# Cansat2019_1516_Payload_SectionA_v04.net
KiCad netlist of a schematic drawn in EAGLE
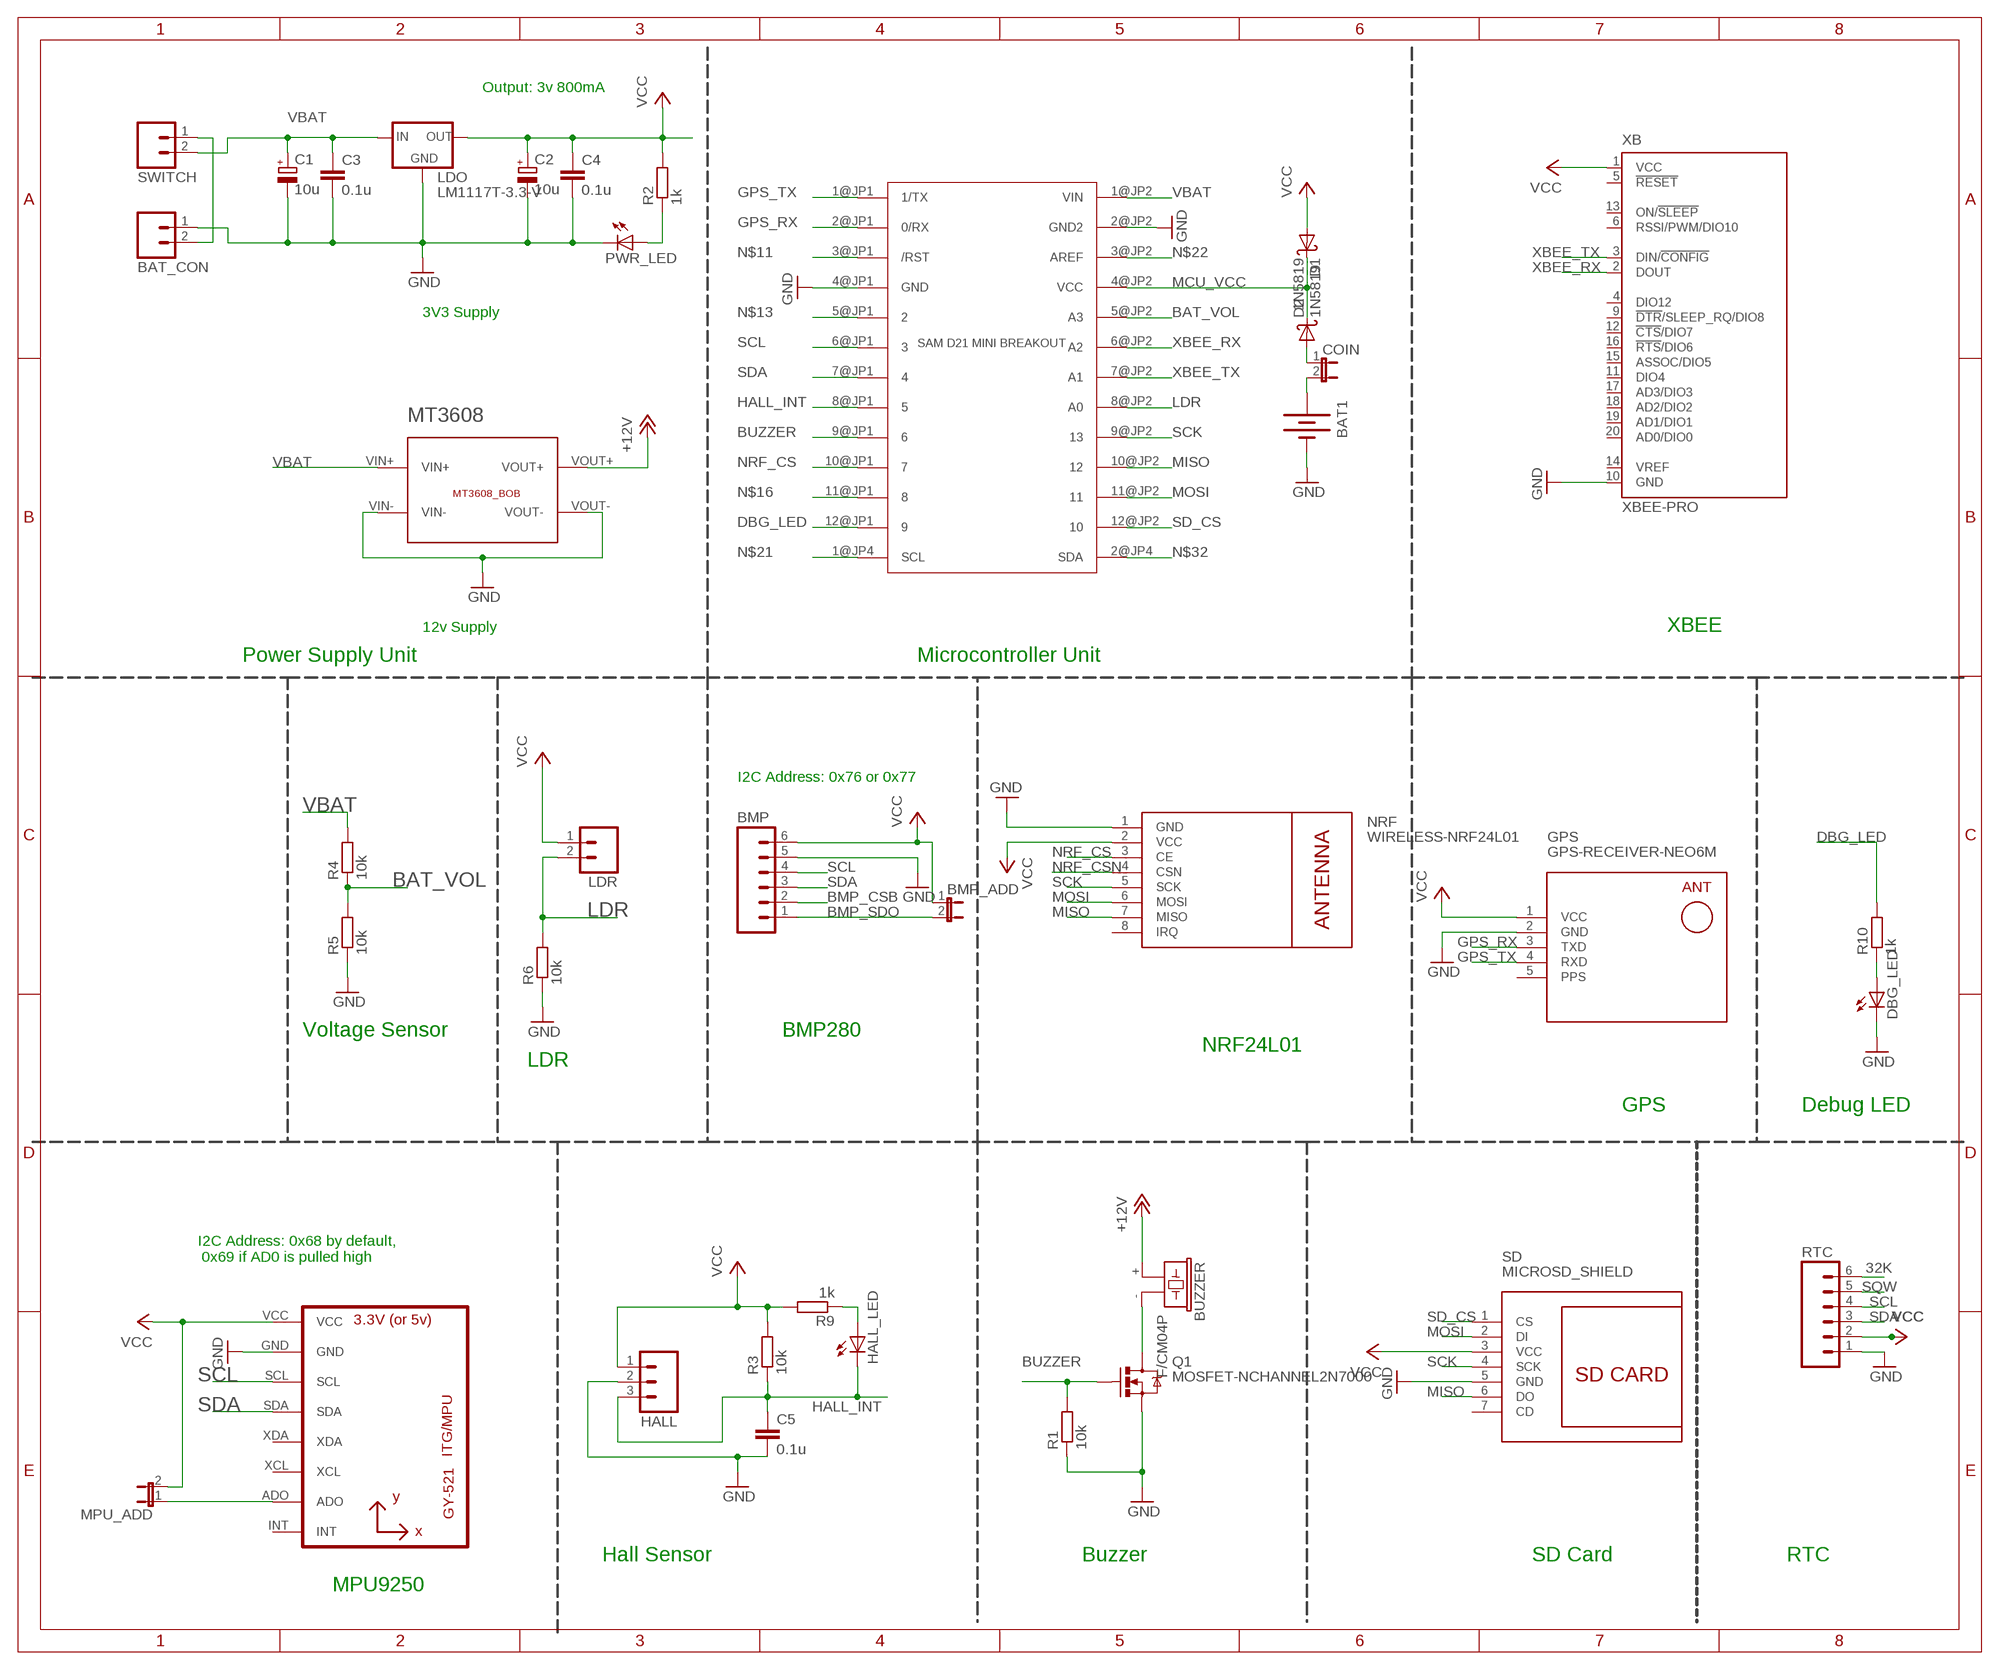
[diagram p0: schematic, sheet 1]

(export (version "E")
  (design (tool "Eeschema 10.0.6"))
  (components
    (comp (ref "BAT1")
      (value "BATTERY20PTH")
      (footprint "eagle-import:BATTCOM_20MM_PTH")
      (libsource (lib "eagle-import") (part "BATTERY20PTH"))
    )
    (comp (ref "BAT_CON")
      (value "M02")
      (footprint "eagle-import:02P")
      (libsource (lib "eagle-import") (part "M02"))
    )
    (comp (ref "BMP")
      (value "M06")
      (footprint "eagle-import:06P")
      (libsource (lib "eagle-import") (part "M06"))
    )
    (comp (ref "BMP_ADD")
      (value "JUMPER-2PTH")
      (footprint "eagle-import:1X02")
      (libsource (lib "eagle-import") (part "JUMPER-2PTH"))
    )
    (comp (ref "BUZZER")
      (value "F/CM04P")
      (footprint "eagle-import:F_CM04P")
      (libsource (lib "eagle-import") (part "F/CM04P"))
    )
    (comp (ref "C1")
      (value "10u")
      (footprint "eagle-import:E2,5-6")
      (libsource (lib "eagle-import") (part "CPOL-EUE2.5-6"))
    )
    (comp (ref "C2")
      (value "10u")
      (footprint "eagle-import:E2,5-6")
      (libsource (lib "eagle-import") (part "CPOL-EUE2.5-6"))
    )
    (comp (ref "C3")
      (value "0.1u")
      (footprint "eagle-import:C025-025X050")
      (libsource (lib "eagle-import") (part "C-EU025-025X050"))
    )
    (comp (ref "C4")
      (value "0.1u")
      (footprint "eagle-import:C025-025X050")
      (libsource (lib "eagle-import") (part "C-EU025-025X050"))
    )
    (comp (ref "C5")
      (value "0.1u")
      (footprint "eagle-import:C025-025X050")
      (libsource (lib "eagle-import") (part "C-EU025-025X050"))
    )
    (comp (ref "COIN")
      (value "JUMPER-2PTH")
      (footprint "eagle-import:1X02")
      (libsource (lib "eagle-import") (part "JUMPER-2PTH"))
    )
    (comp (ref "D1")
      (value "1N5819")
      (footprint "eagle-import:DO41-10")
      (libsource (lib "eagle-import") (part "1N5819"))
    )
    (comp (ref "D2")
      (value "1N5819")
      (footprint "eagle-import:DO41-10")
      (libsource (lib "eagle-import") (part "1N5819"))
    )
    (comp (ref "DBG_LED")
      (value "LED3MM")
      (footprint "eagle-import:LED3MM")
      (libsource (lib "eagle-import") (part "LED3MM"))
    )
    (comp (ref "GPS")
      (value "GPS-RECEIVER-NEO6M")
      (footprint "eagle-import:GPS-RECEIVER-NEO6M")
      (libsource (lib "eagle-import") (part "GPS-RECEIVER-NEO6M"))
    )
    (comp (ref "HALL")
      (value "M03")
      (footprint "eagle-import:03P")
      (libsource (lib "eagle-import") (part "M03"))
    )
    (comp (ref "HALL_LED")
      (value "LED3MM")
      (footprint "eagle-import:LED3MM")
      (libsource (lib "eagle-import") (part "LED3MM"))
    )
    (comp (ref "LDO")
      (value "LM1117T-3.3-V")
      (footprint "eagle-import:TO220V")
      (libsource (lib "eagle-import") (part "LM1117T--V3.3"))
    )
    (comp (ref "LDR")
      (value "M02")
      (footprint "eagle-import:02P")
      (libsource (lib "eagle-import") (part "M02"))
    )
    (comp (ref "MPU")
      (value "GY-521MPU6050")
      (footprint "eagle-import:GY-521")
      (libsource (lib "eagle-import") (part "GY-521MPU6050"))
    )
    (comp (ref "MPU_ADD")
      (value "JUMPER-2PTH")
      (footprint "eagle-import:1X02")
      (libsource (lib "eagle-import") (part "JUMPER-2PTH"))
    )
    (comp (ref "MT3608")
      (value "MT3608_BOB")
      (footprint "eagle-import:MT3608_BOB")
      (libsource (lib "eagle-import") (part "MT3608_BOB"))
    )
    (comp (ref "NRF")
      (value "WIRELESS-NRF24L01")
      (footprint "eagle-import:WIRELESS-NRF24L01")
      (libsource (lib "eagle-import") (part "WIRELESS-NRF24L01"))
    )
    (comp (ref "PWR_LED")
      (value "LED3MM")
      (footprint "eagle-import:LED3MM")
      (libsource (lib "eagle-import") (part "LED3MM"))
    )
    (comp (ref "Q1")
      (value "MOSFET-NCHANNEL2N7000")
      (footprint "eagle-import:TO-92")
      (libsource (lib "eagle-import") (part "MOSFET-NCHANNEL2N7000"))
    )
    (comp (ref "R1")
      (value "10k")
      (footprint "eagle-import:0204_7")
      (libsource (lib "eagle-import") (part "R-EU_0204/7"))
    )
    (comp (ref "R2")
      (value "1k")
      (footprint "eagle-import:0204_7")
      (libsource (lib "eagle-import") (part "R-EU_0204/7"))
    )
    (comp (ref "R3")
      (value "10k")
      (footprint "eagle-import:0204_7")
      (libsource (lib "eagle-import") (part "R-EU_0204/7"))
    )
    (comp (ref "R4")
      (value "10k")
      (footprint "eagle-import:0204_7")
      (libsource (lib "eagle-import") (part "R-EU_0204/7"))
    )
    (comp (ref "R5")
      (value "10k")
      (footprint "eagle-import:0204_7")
      (libsource (lib "eagle-import") (part "R-EU_0204/7"))
    )
    (comp (ref "R6")
      (value "10k")
      (footprint "eagle-import:0204_7")
      (libsource (lib "eagle-import") (part "R-EU_0204/7"))
    )
    (comp (ref "R9")
      (value "1k")
      (footprint "eagle-import:0204_7")
      (libsource (lib "eagle-import") (part "R-EU_0204/7"))
    )
    (comp (ref "R10")
      (value "1k")
      (footprint "eagle-import:0204_7")
      (libsource (lib "eagle-import") (part "R-EU_0204/7"))
    )
    (comp (ref "RTC")
      (value "M06")
      (footprint "eagle-import:06P")
      (libsource (lib "eagle-import") (part "M06"))
    )
    (comp (ref "SAMD")
      (value "SAM_D21_MINI_BREAKOUT")
      (footprint "eagle-import:JP1_SPARKFUN-SAMD21-MINI-BREAKOUT-V10")
      (libsource (lib "eagle-import") (part "SAM_D21_MINI_BREAKOUT"))
    )
    (comp (ref "SD")
      (value "MICROSD_SHIELD")
      (footprint "eagle-import:MICROSD_SHIELD")
      (libsource (lib "eagle-import") (part "MICROSD_SHIELD"))
    )
    (comp (ref "SWITCH")
      (value "M02")
      (footprint "eagle-import:02P")
      (libsource (lib "eagle-import") (part "M02"))
    )
    (comp (ref "XB")
      (value "XBEE-PRO")
      (footprint "eagle-import:XBEE-PRO")
      (fields (field (name "MPN") "XBP24-AWI-001"))
      (libsource (lib "eagle-import") (part "XBEE-PRO"))
    )
  )
  (nets
    (net (code "1") (name "+12V") (class "Default")
      (node (ref "BUZZER") (pin "+") (pinfunction "1_+") (pintype "passive"))
      (node (ref "MT3608") (pin "VOUT+") (pinfunction "VOUT+_VOUT+") (pintype "bidirectional"))
    )
    (net (code "2") (name "/32K") (class "Default")
      (node (ref "RTC") (pin "6") (pinfunction "6_6") (pintype "passive"))
    )
    (net (code "3") (name "/BAT_VOL") (class "Default")
      (node (ref "R4") (pin "1") (pinfunction "1_1") (pintype "passive"))
      (node (ref "R5") (pin "2") (pinfunction "2_2") (pintype "passive"))
      (node (ref "SAMD") (pin "5@JP2") (pinfunction "A3_5@JP2") (pintype "bidirectional"))
    )
    (net (code "4") (name "/BMP_CSB") (class "Default")
      (node (ref "BMP") (pin "2") (pinfunction "2_2") (pintype "passive"))
    )
    (net (code "5") (name "/BMP_SDO") (class "Default")
      (node (ref "BMP") (pin "1") (pinfunction "1_1") (pintype "passive"))
      (node (ref "BMP_ADD") (pin "2") (pinfunction "2_2") (pintype "passive"))
    )
    (net (code "6") (name "/BUZZER") (class "Default")
      (node (ref "Q1") (pin "2") (pinfunction "G_2") (pintype "passive"))
      (node (ref "R1") (pin "2") (pinfunction "2_2") (pintype "passive"))
      (node (ref "SAMD") (pin "9@JP1") (pinfunction "6_9@JP1") (pintype "bidirectional"))
    )
    (net (code "7") (name "/DBG_LED") (class "Default")
      (node (ref "R10") (pin "2") (pinfunction "2_2") (pintype "passive"))
      (node (ref "SAMD") (pin "12@JP1") (pinfunction "9_12@JP1") (pintype "bidirectional"))
    )
    (net (code "8") (name "/GPS_RX") (class "Default")
      (node (ref "GPS") (pin "3") (pinfunction "TXD_3") (pintype "bidirectional"))
      (node (ref "SAMD") (pin "2@JP1") (pinfunction "0/RX_2@JP1") (pintype "bidirectional"))
    )
    (net (code "9") (name "/GPS_TX") (class "Default")
      (node (ref "GPS") (pin "4") (pinfunction "RXD_4") (pintype "power_in"))
      (node (ref "SAMD") (pin "1@JP1") (pinfunction "1/TX_1@JP1") (pintype "bidirectional"))
    )
    (net (code "10") (name "/HALL_INT") (class "Default")
      (node (ref "C5") (pin "1") (pinfunction "1_1") (pintype "passive"))
      (node (ref "HALL") (pin "3") (pinfunction "3_3") (pintype "passive"))
      (node (ref "HALL_LED") (pin "K") (pinfunction "C_K") (pintype "passive"))
      (node (ref "R3") (pin "1") (pinfunction "1_1") (pintype "passive"))
      (node (ref "SAMD") (pin "8@JP1") (pinfunction "5_8@JP1") (pintype "bidirectional"))
    )
    (net (code "11") (name "/LDR") (class "Default")
      (node (ref "LDR") (pin "2") (pinfunction "2_2") (pintype "passive"))
      (node (ref "R6") (pin "2") (pinfunction "2_2") (pintype "passive"))
      (node (ref "SAMD") (pin "8@JP2") (pinfunction "A0_8@JP2") (pintype "bidirectional"))
    )
    (net (code "12") (name "/MCU_VCC") (class "Default")
      (node (ref "D1") (pin "C") (pinfunction "C_C") (pintype "passive"))
      (node (ref "D2") (pin "C") (pinfunction "C_C") (pintype "passive"))
      (node (ref "SAMD") (pin "4@JP2") (pinfunction "VCC_4@JP2") (pintype "power_in"))
    )
    (net (code "13") (name "/MISO") (class "Default")
      (node (ref "NRF") (pin "7") (pinfunction "MISO_7") (pintype "bidirectional"))
      (node (ref "SAMD") (pin "10@JP2") (pinfunction "12_10@JP2") (pintype "bidirectional"))
      (node (ref "SD") (pin "6") (pinfunction "DO_6") (pintype "bidirectional"))
    )
    (net (code "14") (name "/MOSI") (class "Default")
      (node (ref "NRF") (pin "6") (pinfunction "MOSI_6") (pintype "bidirectional"))
      (node (ref "SAMD") (pin "11@JP2") (pinfunction "11_11@JP2") (pintype "bidirectional"))
      (node (ref "SD") (pin "2") (pinfunction "DI_2") (pintype "bidirectional"))
    )
    (net (code "15") (name "/N$11") (class "Default")
      (node (ref "SAMD") (pin "3@JP1") (pinfunction "/RST_3@JP1") (pintype "input"))
    )
    (net (code "16") (name "/N$13") (class "Default")
      (node (ref "SAMD") (pin "5@JP1") (pinfunction "2_5@JP1") (pintype "bidirectional"))
    )
    (net (code "17") (name "/N$16") (class "Default")
      (node (ref "SAMD") (pin "11@JP1") (pinfunction "8_11@JP1") (pintype "bidirectional"))
    )
    (net (code "18") (name "/N$21") (class "Default")
      (node (ref "SAMD") (pin "1@JP4") (pinfunction "SCL_1@JP4") (pintype "bidirectional"))
    )
    (net (code "19") (name "/N$22") (class "Default")
      (node (ref "SAMD") (pin "3@JP2") (pinfunction "AREF_3@JP2") (pintype "power_in"))
    )
    (net (code "20") (name "/N$32") (class "Default")
      (node (ref "SAMD") (pin "2@JP4") (pinfunction "SDA_2@JP4") (pintype "bidirectional"))
    )
    (net (code "21") (name "/NRF_CS") (class "Default")
      (node (ref "NRF") (pin "3") (pinfunction "CE_3") (pintype "bidirectional"))
      (node (ref "SAMD") (pin "10@JP1") (pinfunction "7_10@JP1") (pintype "bidirectional"))
    )
    (net (code "22") (name "/NRF_CSN") (class "Default")
      (node (ref "NRF") (pin "4") (pinfunction "CSN_4") (pintype "bidirectional"))
    )
    (net (code "23") (name "/PPS") (class "Default")
      (node (ref "GPS") (pin "5") (pinfunction "PPS_5") (pintype "power_in"))
    )
    (net (code "24") (name "/SCK") (class "Default")
      (node (ref "NRF") (pin "5") (pinfunction "SCK_5") (pintype "bidirectional"))
      (node (ref "SAMD") (pin "9@JP2") (pinfunction "13_9@JP2") (pintype "bidirectional"))
      (node (ref "SD") (pin "4") (pinfunction "SCK_4") (pintype "bidirectional"))
    )
    (net (code "25") (name "/SCL") (class "Default")
      (node (ref "BMP") (pin "4") (pinfunction "4_4") (pintype "passive"))
      (node (ref "MPU") (pin "SCL") (pinfunction "SCL_SCL") (pintype "bidirectional"))
      (node (ref "RTC") (pin "4") (pinfunction "4_4") (pintype "passive"))
      (node (ref "SAMD") (pin "6@JP1") (pinfunction "3_6@JP1") (pintype "bidirectional"))
    )
    (net (code "26") (name "/SDA") (class "Default")
      (node (ref "BMP") (pin "3") (pinfunction "3_3") (pintype "passive"))
      (node (ref "MPU") (pin "SDA") (pinfunction "SDA_SDA") (pintype "bidirectional"))
      (node (ref "RTC") (pin "3") (pinfunction "3_3") (pintype "passive"))
      (node (ref "SAMD") (pin "7@JP1") (pinfunction "4_7@JP1") (pintype "bidirectional"))
    )
    (net (code "27") (name "/SD_CS") (class "Default")
      (node (ref "SAMD") (pin "12@JP2") (pinfunction "10_12@JP2") (pintype "bidirectional"))
      (node (ref "SD") (pin "1") (pinfunction "CS_1") (pintype "bidirectional"))
    )
    (net (code "28") (name "/SQW") (class "Default")
      (node (ref "RTC") (pin "5") (pinfunction "5_5") (pintype "passive"))
    )
    (net (code "29") (name "/VBAT") (class "Default")
      (node (ref "C1") (pin "+") (pinfunction "+_+") (pintype "passive"))
      (node (ref "C3") (pin "1") (pinfunction "1_1") (pintype "passive"))
      (node (ref "LDO") (pin "3") (pinfunction "IN_3") (pintype "input"))
      (node (ref "MT3608") (pin "VIN+") (pinfunction "VIN+_VIN+") (pintype "bidirectional"))
      (node (ref "R4") (pin "2") (pinfunction "2_2") (pintype "passive"))
      (node (ref "SAMD") (pin "1@JP2") (pinfunction "VIN_1@JP2") (pintype "power_in"))
      (node (ref "SWITCH") (pin "2") (pinfunction "2_2") (pintype "passive"))
    )
    (net (code "30") (name "/XBEE_RX") (class "Default")
      (node (ref "SAMD") (pin "6@JP2") (pinfunction "A2_6@JP2") (pintype "bidirectional"))
      (node (ref "XB") (pin "2") (pinfunction "DOUT_2") (pintype "output"))
    )
    (net (code "31") (name "/XBEE_TX") (class "Default")
      (node (ref "SAMD") (pin "7@JP2") (pinfunction "A1_7@JP2") (pintype "bidirectional"))
      (node (ref "XB") (pin "3") (pinfunction "DIN/~{CONFIG}_3") (pintype "input"))
    )
    (net (code "32") (name "GND") (class "Default")
      (node (ref "BAT1") (pin "2") (pinfunction "-_2") (pintype "power_in"))
      (node (ref "BAT_CON") (pin "1") (pinfunction "1_1") (pintype "passive"))
      (node (ref "BMP") (pin "5") (pinfunction "5_5") (pintype "passive"))
      (node (ref "C1") (pin "-") (pinfunction "-_-") (pintype "passive"))
      (node (ref "C2") (pin "-") (pinfunction "-_-") (pintype "passive"))
      (node (ref "C3") (pin "2") (pinfunction "2_2") (pintype "passive"))
      (node (ref "C4") (pin "2") (pinfunction "2_2") (pintype "passive"))
      (node (ref "C5") (pin "2") (pinfunction "2_2") (pintype "passive"))
      (node (ref "DBG_LED") (pin "K") (pinfunction "C_K") (pintype "passive"))
      (node (ref "GPS") (pin "2") (pinfunction "GND_2") (pintype "bidirectional"))
      (node (ref "HALL") (pin "2") (pinfunction "2_2") (pintype "passive"))
      (node (ref "LDO") (pin "1") (pinfunction "GND_1") (pintype "input"))
      (node (ref "MPU") (pin "GND") (pinfunction "GND_GND") (pintype "bidirectional"))
      (node (ref "MT3608") (pin "VIN-") (pinfunction "VIN-_VIN-") (pintype "bidirectional"))
      (node (ref "MT3608") (pin "VOUT-") (pinfunction "VOUT-_VOUT-") (pintype "bidirectional"))
      (node (ref "NRF") (pin "1") (pinfunction "GND_1") (pintype "power_in"))
      (node (ref "PWR_LED") (pin "K") (pinfunction "C_K") (pintype "passive"))
      (node (ref "Q1") (pin "1") (pinfunction "S_1") (pintype "passive"))
      (node (ref "R1") (pin "1") (pinfunction "1_1") (pintype "passive"))
      (node (ref "R5") (pin "1") (pinfunction "1_1") (pintype "passive"))
      (node (ref "R6") (pin "1") (pinfunction "1_1") (pintype "passive"))
      (node (ref "RTC") (pin "1") (pinfunction "1_1") (pintype "passive"))
      (node (ref "SAMD") (pin "2@JP2") (pinfunction "GND2_2@JP2") (pintype "power_in"))
      (node (ref "SAMD") (pin "4@JP1") (pinfunction "GND_4@JP1") (pintype "power_in"))
      (node (ref "SD") (pin "5") (pinfunction "GND_5") (pintype "power_in"))
      (node (ref "XB") (pin "10") (pinfunction "GND_10") (pintype "power_in"))
    )
    (net (code "33") (name "Net-(BAT1-+)") (class "Default")
      (node (ref "BAT1") (pin "1") (pinfunction "+_1") (pintype "power_in"))
      (node (ref "COIN") (pin "2") (pinfunction "2_2") (pintype "passive"))
    )
    (net (code "34") (name "Net-(BAT_CON-Pad2)") (class "Default")
      (node (ref "BAT_CON") (pin "2") (pinfunction "2_2") (pintype "passive"))
      (node (ref "SWITCH") (pin "1") (pinfunction "1_1") (pintype "passive"))
    )
    (net (code "35") (name "Net-(BUZZER-2)") (class "Default")
      (node (ref "BUZZER") (pin "-") (pinfunction "2_-") (pintype "passive"))
      (node (ref "Q1") (pin "3") (pinfunction "D_3") (pintype "passive"))
    )
    (net (code "36") (name "Net-(COIN-Pad1)") (class "Default")
      (node (ref "COIN") (pin "1") (pinfunction "1_1") (pintype "passive"))
      (node (ref "D2") (pin "A") (pinfunction "A_A") (pintype "passive"))
    )
    (net (code "37") (name "Net-(DBG_LED-PadA)") (class "Default")
      (node (ref "DBG_LED") (pin "A") (pinfunction "A_A") (pintype "passive"))
      (node (ref "R10") (pin "1") (pinfunction "1_1") (pintype "passive"))
    )
    (net (code "38") (name "Net-(HALL_LED-PadA)") (class "Default")
      (node (ref "HALL_LED") (pin "A") (pinfunction "A_A") (pintype "passive"))
      (node (ref "R9") (pin "1") (pinfunction "1_1") (pintype "passive"))
    )
    (net (code "39") (name "Net-(MPU-PadADO)") (class "Default")
      (node (ref "MPU") (pin "ADO") (pinfunction "ADO_ADO") (pintype "bidirectional"))
      (node (ref "MPU_ADD") (pin "1") (pinfunction "1_1") (pintype "passive"))
    )
    (net (code "40") (name "Net-(PWR_LED-PadA)") (class "Default")
      (node (ref "PWR_LED") (pin "A") (pinfunction "A_A") (pintype "passive"))
      (node (ref "R2") (pin "1") (pinfunction "1_1") (pintype "passive"))
    )
    (net (code "41") (name "VCC") (class "Default")
      (node (ref "BMP") (pin "6") (pinfunction "6_6") (pintype "passive"))
      (node (ref "BMP_ADD") (pin "1") (pinfunction "1_1") (pintype "passive"))
      (node (ref "C2") (pin "+") (pinfunction "+_+") (pintype "passive"))
      (node (ref "C4") (pin "1") (pinfunction "1_1") (pintype "passive"))
      (node (ref "D1") (pin "A") (pinfunction "A_A") (pintype "passive"))
      (node (ref "GPS") (pin "1") (pinfunction "VCC_1") (pintype "bidirectional"))
      (node (ref "HALL") (pin "1") (pinfunction "1_1") (pintype "passive"))
      (node (ref "LDO") (pin "2") (pinfunction "OUT_2") (pintype "passive"))
      (node (ref "LDR") (pin "1") (pinfunction "1_1") (pintype "passive"))
      (node (ref "MPU") (pin "VCC") (pinfunction "VCC_VCC") (pintype "bidirectional"))
      (node (ref "MPU_ADD") (pin "2") (pinfunction "2_2") (pintype "passive"))
      (node (ref "NRF") (pin "2") (pinfunction "VCC_2") (pintype "power_in"))
      (node (ref "R2") (pin "2") (pinfunction "2_2") (pintype "passive"))
      (node (ref "R3") (pin "2") (pinfunction "2_2") (pintype "passive"))
      (node (ref "R9") (pin "2") (pinfunction "2_2") (pintype "passive"))
      (node (ref "RTC") (pin "2") (pinfunction "2_2") (pintype "passive"))
      (node (ref "SD") (pin "3") (pinfunction "VCC_3") (pintype "power_in"))
      (node (ref "XB") (pin "1") (pinfunction "VCC_1") (pintype "power_in"))
    )
    (net (code "42") (name "unconnected-(MPU-PadINT)") (class "Default")
      (node (ref "MPU") (pin "INT") (pinfunction "INT_INT") (pintype "bidirectional"))
    )
    (net (code "43") (name "unconnected-(MPU-PadXCL)") (class "Default")
      (node (ref "MPU") (pin "XCL") (pinfunction "XCL_XCL") (pintype "bidirectional"))
    )
    (net (code "44") (name "unconnected-(MPU-PadXDA)") (class "Default")
      (node (ref "MPU") (pin "XDA") (pinfunction "XDA_XDA") (pintype "bidirectional"))
    )
    (net (code "45") (name "unconnected-(NRF-IRQ-Pad8)") (class "Default")
      (node (ref "NRF") (pin "8") (pinfunction "IRQ_8") (pintype "bidirectional"))
    )
    (net (code "46") (name "unconnected-(SD-CD-Pad7)") (class "Default")
      (node (ref "SD") (pin "7") (pinfunction "CD_7") (pintype "bidirectional"))
    )
    (net (code "47") (name "unconnected-(XB-AD0{slash}DIO0-Pad20)") (class "Default")
      (node (ref "XB") (pin "20") (pinfunction "AD0/DIO0_20") (pintype "bidirectional"))
    )
    (net (code "48") (name "unconnected-(XB-AD1{slash}DIO1-Pad19)") (class "Default")
      (node (ref "XB") (pin "19") (pinfunction "AD1/DIO1_19") (pintype "bidirectional"))
    )
    (net (code "49") (name "unconnected-(XB-AD2{slash}DIO2-Pad18)") (class "Default")
      (node (ref "XB") (pin "18") (pinfunction "AD2/DIO2_18") (pintype "bidirectional"))
    )
    (net (code "50") (name "unconnected-(XB-AD3{slash}DIO3-Pad17)") (class "Default")
      (node (ref "XB") (pin "17") (pinfunction "AD3/DIO3_17") (pintype "bidirectional"))
    )
    (net (code "51") (name "unconnected-(XB-ASSOC{slash}DIO5-Pad15)") (class "Default")
      (node (ref "XB") (pin "15") (pinfunction "ASSOC/DIO5_15") (pintype "bidirectional"))
    )
    (net (code "52") (name "unconnected-(XB-DIO4-Pad11)") (class "Default")
      (node (ref "XB") (pin "11") (pinfunction "DIO4_11") (pintype "bidirectional"))
    )
    (net (code "53") (name "unconnected-(XB-DIO12-Pad4)") (class "Default")
      (node (ref "XB") (pin "4") (pinfunction "DIO12_4") (pintype "bidirectional"))
    )
    (net (code "54") (name "unconnected-(XB-ON{slash}~{SLEEP}-Pad13)") (class "Default")
      (node (ref "XB") (pin "13") (pinfunction "ON/~{SLEEP}_13") (pintype "output"))
    )
    (net (code "55") (name "unconnected-(XB-RSSI{slash}PWM{slash}DIO10-Pad6)") (class "Default")
      (node (ref "XB") (pin "6") (pinfunction "RSSI/PWM/DIO10_6") (pintype "output"))
    )
    (net (code "56") (name "unconnected-(XB-VREF-Pad14)") (class "Default")
      (node (ref "XB") (pin "14") (pinfunction "VREF_14") (pintype "input"))
    )
    (net (code "57") (name "unconnected-(XB-~{CTS}{slash}DIO7-Pad12)") (class "Default")
      (node (ref "XB") (pin "12") (pinfunction "~{CTS}/DIO7_12") (pintype "bidirectional"))
    )
    (net (code "58") (name "unconnected-(XB-~{DTR}{slash}SLEEP_RQ{slash}DIO8-Pad9)") (class "Default")
      (node (ref "XB") (pin "9") (pinfunction "~{DTR}/SLEEP_RQ/DIO8_9") (pintype "bidirectional"))
    )
    (net (code "59") (name "unconnected-(XB-~{RESET}-Pad5)") (class "Default")
      (node (ref "XB") (pin "5") (pinfunction "~{RESET}_5") (pintype "input"))
    )
    (net (code "60") (name "unconnected-(XB-~{RTS}{slash}DIO6-Pad16)") (class "Default")
      (node (ref "XB") (pin "16") (pinfunction "~{RTS}/DIO6_16") (pintype "bidirectional"))
    )
  )
)
